# ethernet.net
KiCad netlist of a schematic drawn in Altium Designer
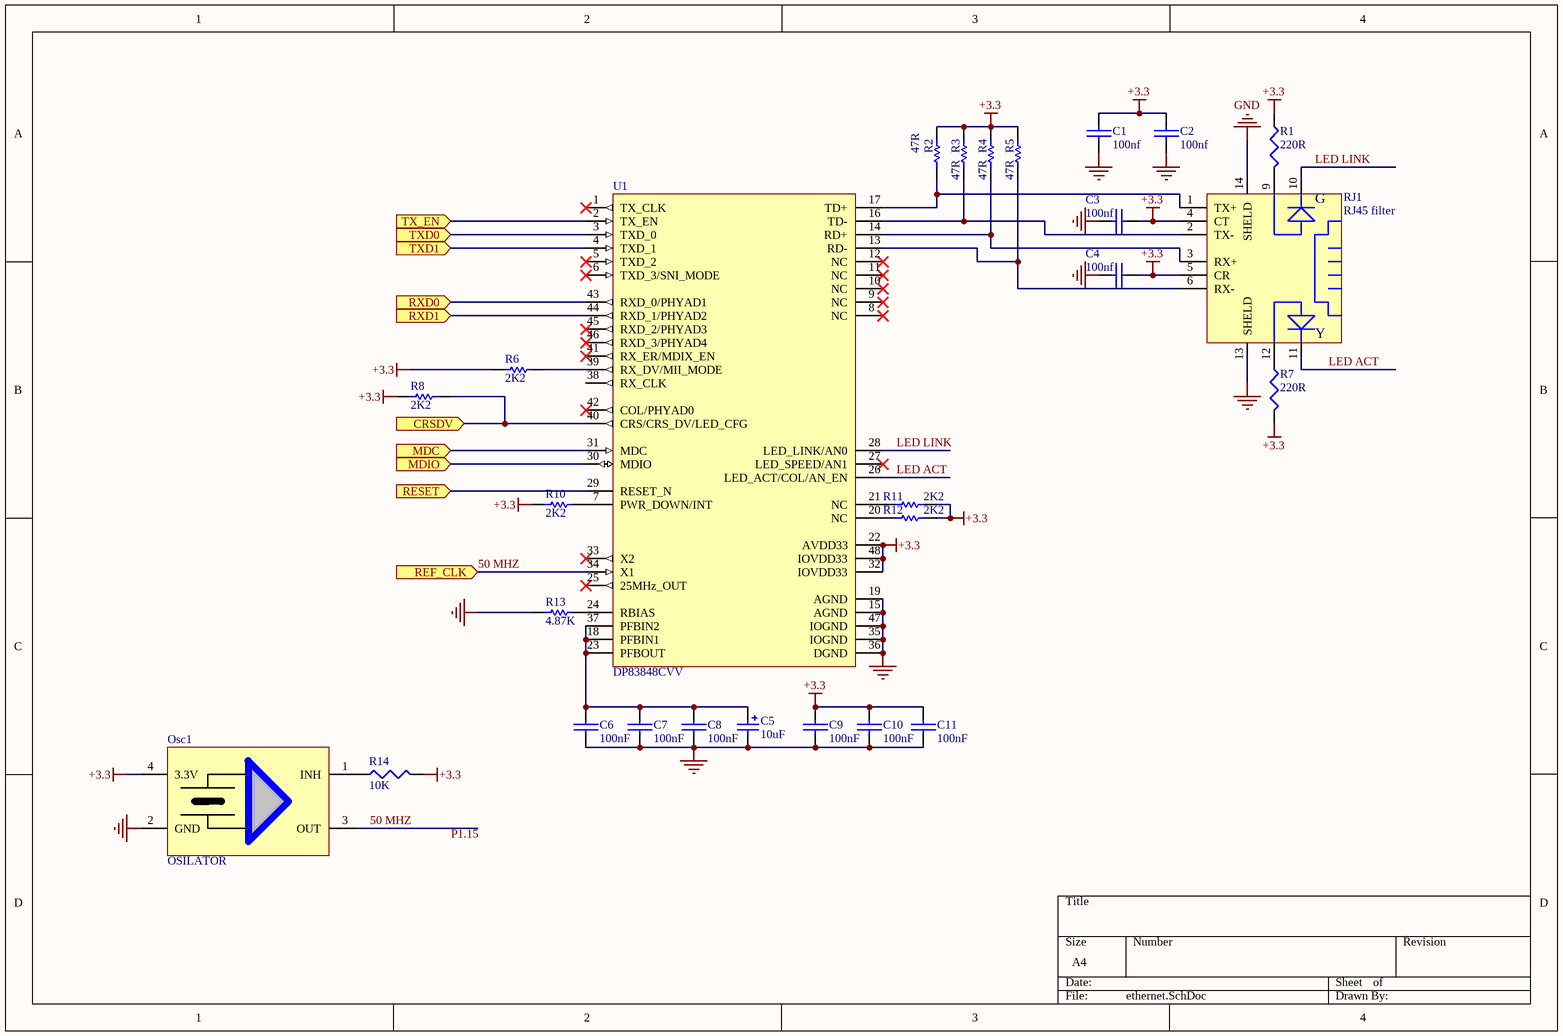
[diagram p0: ethernet.SchDoc]

(export (version "E")
  (design (tool "Eeschema 10.0.6"))
  (components
    (comp (ref "C1") (value "100nf") (footprint "1206") (libsource (lib "") (part "CAP_1")))
    (comp (ref "C2") (value "100nf") (footprint "1206") (libsource (lib "") (part "CAP_1")))
    (comp (ref "C3") (value "100nf") (footprint "1206") (libsource (lib "") (part "CAP_1")))
    (comp (ref "C4") (value "100nf") (footprint "1206") (libsource (lib "") (part "CAP_1")))
    (comp (ref "C5")
      (value "10uF")
      (footprint "cap10")
      (description "Polarized Capacitor (Radial)")
      (fields (field (name "PUBLISHER") "Altium Limited"))
      (libsource (lib "Miscellaneous Devices") (part "Cap Pol1"))
    )
    (comp (ref "C6")
      (value "100nF")
      (footprint "0805")
      (description "Capacitor")
      (libsource (lib "*") (part "CAP"))
    )
    (comp (ref "C7")
      (value "100nF")
      (footprint "0805")
      (description "Capacitor")
      (libsource (lib "*") (part "CAP"))
    )
    (comp (ref "C8")
      (value "100nF")
      (footprint "0805")
      (description "Capacitor")
      (libsource (lib "*") (part "CAP"))
    )
    (comp (ref "C9")
      (value "100nF")
      (footprint "0805")
      (description "Capacitor")
      (libsource (lib "*") (part "CAP"))
    )
    (comp (ref "C10")
      (value "100nF")
      (footprint "0805")
      (description "Capacitor")
      (libsource (lib "*") (part "CAP"))
    )
    (comp (ref "C11")
      (value "100nF")
      (footprint "0805")
      (description "Capacitor")
      (libsource (lib "*") (part "CAP"))
    )
    (comp (ref "Osc1")
      (value "OSILATOR")
      (footprint "XTAL_5X7")
      (libsource (lib "New Lib") (part "OSILATOR"))
    )
    (comp (ref "R1")
      (value "220R")
      (footprint "1206")
      (description "Resistor")
      (fields (field (name "PUBLISHER") "Altium Limited"))
      (libsource (lib "Miscellaneous Devices") (part "Res3"))
    )
    (comp (ref "R2")
      (value "47R")
      (footprint "1206")
      (description "Resistor")
      (fields (field (name "PUBLISHER") "Altium Limited"))
      (libsource (lib "Miscellaneous Devices") (part "Res1"))
    )
    (comp (ref "R3")
      (value "47R")
      (footprint "1206")
      (description "Resistor")
      (fields (field (name "PUBLISHER") "Altium Limited"))
      (libsource (lib "Miscellaneous Devices") (part "Res1"))
    )
    (comp (ref "R4")
      (value "47R")
      (footprint "1206")
      (description "Resistor")
      (fields (field (name "PUBLISHER") "Altium Limited"))
      (libsource (lib "Miscellaneous Devices") (part "Res1"))
    )
    (comp (ref "R5")
      (value "47R")
      (footprint "1206")
      (description "Resistor")
      (fields (field (name "PUBLISHER") "Altium Limited"))
      (libsource (lib "Miscellaneous Devices") (part "Res1"))
    )
    (comp (ref "R6")
      (value "2K2")
      (footprint "1206")
      (description "Resistor")
      (fields (field (name "PUBLISHER") "Altium Limited"))
      (libsource (lib "Miscellaneous Devices") (part "Res1"))
    )
    (comp (ref "R7")
      (value "220R")
      (footprint "1206")
      (description "Resistor")
      (fields (field (name "PUBLISHER") "Altium Limited"))
      (libsource (lib "Miscellaneous Devices") (part "Res3"))
    )
    (comp (ref "R8")
      (value "2K2")
      (footprint "1206")
      (description "Resistor")
      (fields (field (name "PUBLISHER") "Altium Limited"))
      (libsource (lib "Miscellaneous Devices") (part "Res1"))
    )
    (comp (ref "R10")
      (value "2K2")
      (footprint "1206")
      (description "Resistor")
      (fields (field (name "PUBLISHER") "Altium Limited"))
      (libsource (lib "Miscellaneous Devices") (part "Res1"))
    )
    (comp (ref "R11")
      (value "2K2")
      (footprint "1206")
      (description "Resistor")
      (fields (field (name "PUBLISHER") "Altium Limited"))
      (libsource (lib "Miscellaneous Devices") (part "Res1"))
    )
    (comp (ref "R12")
      (value "2K2")
      (footprint "1206")
      (description "Resistor")
      (fields (field (name "PUBLISHER") "Altium Limited"))
      (libsource (lib "Miscellaneous Devices") (part "Res1"))
    )
    (comp (ref "R13")
      (value "4.87K")
      (footprint "1206")
      (description "Resistor")
      (fields (field (name "PUBLISHER") "Altium Limited"))
      (libsource (lib "Miscellaneous Devices") (part "Res1"))
    )
    (comp (ref "R14")
      (value "10K")
      (footprint "1206")
      (description "Resistor")
      (fields (field (name "PUBLISHER") "Altium Limited"))
      (libsource (lib "Miscellaneous Devices") (part "Res3"))
    )
    (comp (ref "RJ1")
      (value "RJ45 filter")
      (footprint "RJ45LED")
      (libsource (lib "Schlib1") (part "RJ45_led_filter"))
    )
    (comp (ref "U1")
      (value "DP83848CVV")
      (footprint "TQFP48_M")
      (libsource (lib "MB784") (part "DP83848CVV"))
    )
  )
  (nets
    (net (code "1") (name "+3.3") (class "Default")
      (node (ref "C1") (pin "2") (pintype "passive"))
      (node (ref "C10") (pin "2") (pinfunction "2_2") (pintype "passive"))
      (node (ref "C11") (pin "2") (pinfunction "2_2") (pintype "passive"))
      (node (ref "C2") (pin "2") (pintype "passive"))
      (node (ref "C3") (pin "2") (pintype "passive"))
      (node (ref "C4") (pin "2") (pintype "passive"))
      (node (ref "C9") (pin "1") (pinfunction "1_1") (pintype "passive"))
      (node (ref "Osc1") (pin "4") (pinfunction "3.3V_4") (pintype "passive"))
      (node (ref "R1") (pin "1") (pinfunction "1_1") (pintype "passive"))
      (node (ref "R10") (pin "1") (pinfunction "1_1") (pintype "passive"))
      (node (ref "R11") (pin "2") (pinfunction "2_2") (pintype "passive"))
      (node (ref "R12") (pin "2") (pinfunction "2_2") (pintype "passive"))
      (node (ref "R14") (pin "2") (pinfunction "2_2") (pintype "passive"))
      (node (ref "R2") (pin "2") (pinfunction "2_2") (pintype "passive"))
      (node (ref "R3") (pin "2") (pinfunction "2_2") (pintype "passive"))
      (node (ref "R4") (pin "2") (pinfunction "2_2") (pintype "passive"))
      (node (ref "R5") (pin "2") (pinfunction "2_2") (pintype "passive"))
      (node (ref "R6") (pin "1") (pinfunction "1_1") (pintype "passive"))
      (node (ref "R7") (pin "1") (pinfunction "1_1") (pintype "passive"))
      (node (ref "R8") (pin "1") (pinfunction "1_1") (pintype "passive"))
      (node (ref "RJ1") (pin "4") (pinfunction "CT_4") (pintype "passive"))
      (node (ref "RJ1") (pin "5") (pinfunction "CR_5") (pintype "passive"))
      (node (ref "U1") (pin "22") (pinfunction "AVDD33_22") (pintype "passive"))
      (node (ref "U1") (pin "32") (pinfunction "IOVDD33_32") (pintype "passive"))
      (node (ref "U1") (pin "48") (pinfunction "IOVDD33_48") (pintype "passive"))
    )
    (net (code "2") (name "/50 MHZ") (class "Default")
      (node (ref "Osc1") (pin "3") (pinfunction "OUT_3") (pintype "passive"))
      (node (ref "U1") (pin "34") (pinfunction "X1_34") (pintype "input"))
    )
    (net (code "3") (name "/CRSDV") (class "Default")
      (node (ref "R8") (pin "2") (pinfunction "2_2") (pintype "passive"))
      (node (ref "U1") (pin "40") (pinfunction "CRS/CRS_DV/LED_CFG_40") (pintype "output"))
    )
    (net (code "4") (name "/LED ACT") (class "Default")
      (node (ref "RJ1") (pin "11") (pinfunction "ledy-_11") (pintype "passive"))
      (node (ref "U1") (pin "26") (pinfunction "LED_ACT/COL/AN_EN_26") (pintype "passive"))
    )
    (net (code "5") (name "/LED LINK") (class "Default")
      (node (ref "RJ1") (pin "10") (pinfunction "ledg-_10") (pintype "passive"))
      (node (ref "U1") (pin "28") (pinfunction "LED_LINK/AN0_28") (pintype "passive"))
    )
    (net (code "6") (name "/MDC") (class "Default")
      (node (ref "U1") (pin "31") (pinfunction "MDC_31") (pintype "input"))
    )
    (net (code "7") (name "/MDIO") (class "Default")
      (node (ref "U1") (pin "30") (pinfunction "MDIO_30") (pintype "bidirectional"))
    )
    (net (code "9") (name "/RESET") (class "Default")
      (node (ref "U1") (pin "29") (pinfunction "RESET_N_29") (pintype "passive"))
    )
    (net (code "10") (name "/RXD0") (class "Default")
      (node (ref "U1") (pin "43") (pinfunction "RXD_0/PHYAD1_43") (pintype "output"))
    )
    (net (code "11") (name "/RXD1") (class "Default")
      (node (ref "U1") (pin "44") (pinfunction "RXD_1/PHYAD2_44") (pintype "output"))
    )
    (net (code "12") (name "/TXD0") (class "Default")
      (node (ref "U1") (pin "3") (pinfunction "TXD_0_3") (pintype "input"))
    )
    (net (code "13") (name "/TXD1") (class "Default")
      (node (ref "U1") (pin "4") (pinfunction "TXD_1_4") (pintype "input"))
    )
    (net (code "14") (name "/TX_EN") (class "Default")
      (node (ref "U1") (pin "2") (pinfunction "TX_EN_2") (pintype "input"))
    )
    (net (code "15") (name "GND") (class "Default")
      (node (ref "C1") (pin "1") (pintype "passive"))
      (node (ref "C10") (pin "1") (pinfunction "1_1") (pintype "passive"))
      (node (ref "C11") (pin "1") (pinfunction "1_1") (pintype "passive"))
      (node (ref "C2") (pin "1") (pintype "passive"))
      (node (ref "C3") (pin "1") (pintype "passive"))
      (node (ref "C4") (pin "1") (pintype "passive"))
      (node (ref "C5") (pin "2") (pinfunction "2_2") (pintype "passive"))
      (node (ref "C6") (pin "2") (pinfunction "2_2") (pintype "passive"))
      (node (ref "C7") (pin "1") (pinfunction "1_1") (pintype "passive"))
      (node (ref "C8") (pin "1") (pinfunction "1_1") (pintype "passive"))
      (node (ref "C9") (pin "2") (pinfunction "2_2") (pintype "passive"))
      (node (ref "Osc1") (pin "2") (pinfunction "GND_2") (pintype "passive"))
      (node (ref "R13") (pin "1") (pinfunction "1_1") (pintype "passive"))
      (node (ref "RJ1") (pin "13") (pinfunction "SHELD_13") (pintype "passive"))
      (node (ref "RJ1") (pin "14") (pinfunction "SHELD_14") (pintype "passive"))
      (node (ref "U1") (pin "15") (pinfunction "AGND_15") (pintype "passive"))
      (node (ref "U1") (pin "19") (pinfunction "AGND_19") (pintype "passive"))
      (node (ref "U1") (pin "35") (pinfunction "IOGND_35") (pintype "passive"))
      (node (ref "U1") (pin "36") (pinfunction "DGND_36") (pintype "passive"))
      (node (ref "U1") (pin "47") (pinfunction "IOGND_47") (pintype "passive"))
    )
    (net (code "16") (name "Net-(Osc1-INH)") (class "Default")
      (node (ref "Osc1") (pin "1") (pinfunction "INH_1") (pintype "passive"))
      (node (ref "R14") (pin "1") (pinfunction "1_1") (pintype "passive"))
    )
    (net (code "17") (name "Net-(R11-Pad1)") (class "Default")
      (node (ref "R11") (pin "1") (pinfunction "1_1") (pintype "passive"))
      (node (ref "U1") (pin "21") (pinfunction "NC_21") (pintype "passive"))
    )
    (net (code "18") (name "Net-(R12-Pad1)") (class "Default")
      (node (ref "R12") (pin "1") (pinfunction "1_1") (pintype "passive"))
      (node (ref "U1") (pin "20") (pinfunction "NC_20") (pintype "passive"))
    )
    (net (code "19") (name "Net-(RJ1-RX+)") (class "Default")
      (node (ref "R4") (pin "1") (pinfunction "1_1") (pintype "passive"))
      (node (ref "RJ1") (pin "3") (pinfunction "RX+_3") (pintype "passive"))
      (node (ref "U1") (pin "14") (pinfunction "RD+_14") (pintype "passive"))
    )
    (net (code "20") (name "Net-(RJ1-RX-)") (class "Default")
      (node (ref "R5") (pin "1") (pinfunction "1_1") (pintype "passive"))
      (node (ref "RJ1") (pin "6") (pinfunction "RX-_6") (pintype "passive"))
      (node (ref "U1") (pin "13") (pinfunction "RD-_13") (pintype "passive"))
    )
    (net (code "21") (name "Net-(RJ1-TX+)") (class "Default")
      (node (ref "R2") (pin "1") (pinfunction "1_1") (pintype "passive"))
      (node (ref "RJ1") (pin "1") (pinfunction "TX+_1") (pintype "passive"))
      (node (ref "U1") (pin "17") (pinfunction "TD+_17") (pintype "passive"))
    )
    (net (code "22") (name "Net-(RJ1-TX-)") (class "Default")
      (node (ref "R3") (pin "1") (pinfunction "1_1") (pintype "passive"))
      (node (ref "RJ1") (pin "2") (pinfunction "TX-_2") (pintype "passive"))
      (node (ref "U1") (pin "16") (pinfunction "TD-_16") (pintype "passive"))
    )
    (net (code "23") (name "Net-(RJ1-ledg+)") (class "Default")
      (node (ref "R1") (pin "2") (pinfunction "2_2") (pintype "passive"))
      (node (ref "RJ1") (pin "9") (pinfunction "ledg+_9") (pintype "passive"))
    )
    (net (code "24") (name "Net-(RJ1-ledy+)") (class "Default")
      (node (ref "R7") (pin "2") (pinfunction "2_2") (pintype "passive"))
      (node (ref "RJ1") (pin "12") (pinfunction "ledy+_12") (pintype "passive"))
    )
    (net (code "25") (name "Net-(U1-PFBIN1)") (class "Default")
      (node (ref "C5") (pin "1") (pinfunction "1_1") (pintype "passive"))
      (node (ref "C6") (pin "1") (pinfunction "1_1") (pintype "passive"))
      (node (ref "C7") (pin "2") (pinfunction "2_2") (pintype "passive"))
      (node (ref "C8") (pin "2") (pinfunction "2_2") (pintype "passive"))
      (node (ref "U1") (pin "18") (pinfunction "PFBIN1_18") (pintype "passive"))
      (node (ref "U1") (pin "23") (pinfunction "PFBOUT_23") (pintype "passive"))
      (node (ref "U1") (pin "37") (pinfunction "PFBIN2_37") (pintype "passive"))
    )
    (net (code "26") (name "Net-(U1-PWR_DOWN{slash}INT)") (class "Default")
      (node (ref "R10") (pin "2") (pinfunction "2_2") (pintype "passive"))
      (node (ref "U1") (pin "7") (pinfunction "PWR_DOWN/INT_7") (pintype "passive"))
    )
    (net (code "27") (name "Net-(U1-RBIAS)") (class "Default")
      (node (ref "R13") (pin "2") (pinfunction "2_2") (pintype "passive"))
      (node (ref "U1") (pin "24") (pinfunction "RBIAS_24") (pintype "passive"))
    )
    (net (code "28") (name "Net-(U1-RX_DV{slash}MII_MODE)") (class "Default")
      (node (ref "R6") (pin "2") (pinfunction "2_2") (pintype "passive"))
      (node (ref "U1") (pin "39") (pinfunction "RX_DV/MII_MODE_39") (pintype "output"))
    )
    (net (code "29") (name "unconnected-(U1-25MHz_OUT-Pad25)") (class "Default")
      (node (ref "U1") (pin "25") (pinfunction "25MHz_OUT_25") (pintype "output+no_connect"))
    )
    (net (code "30") (name "unconnected-(U1-COL{slash}PHYAD0-Pad42)") (class "Default")
      (node (ref "U1") (pin "42") (pinfunction "COL/PHYAD0_42") (pintype "output+no_connect"))
    )
    (net (code "31") (name "unconnected-(U1-LED_SPEED{slash}AN1-Pad27)") (class "Default")
      (node (ref "U1") (pin "27") (pinfunction "LED_SPEED/AN1_27") (pintype "passive+no_connect"))
    )
    (net (code "32") (name "unconnected-(U1-NC-Pad8)") (class "Default")
      (node (ref "U1") (pin "8") (pinfunction "NC_8") (pintype "passive+no_connect"))
    )
    (net (code "33") (name "unconnected-(U1-NC-Pad9)") (class "Default")
      (node (ref "U1") (pin "9") (pinfunction "NC_9") (pintype "passive+no_connect"))
    )
    (net (code "34") (name "unconnected-(U1-NC-Pad10)") (class "Default")
      (node (ref "U1") (pin "10") (pinfunction "NC_10") (pintype "passive+no_connect"))
    )
    (net (code "35") (name "unconnected-(U1-NC-Pad11)") (class "Default")
      (node (ref "U1") (pin "11") (pinfunction "NC_11") (pintype "passive+no_connect"))
    )
    (net (code "36") (name "unconnected-(U1-NC-Pad12)") (class "Default")
      (node (ref "U1") (pin "12") (pinfunction "NC_12") (pintype "passive+no_connect"))
    )
    (net (code "37") (name "unconnected-(U1-RXD_2{slash}PHYAD3-Pad45)") (class "Default")
      (node (ref "U1") (pin "45") (pinfunction "RXD_2/PHYAD3_45") (pintype "output+no_connect"))
    )
    (net (code "38") (name "unconnected-(U1-RXD_3{slash}PHYAD4-Pad46)") (class "Default")
      (node (ref "U1") (pin "46") (pinfunction "RXD_3/PHYAD4_46") (pintype "output+no_connect"))
    )
    (net (code "39") (name "unconnected-(U1-RX_CLK-Pad38)") (class "Default")
      (node (ref "U1") (pin "38") (pinfunction "RX_CLK_38") (pintype "output"))
    )
    (net (code "40") (name "unconnected-(U1-RX_ER{slash}MDIX_EN-Pad41)") (class "Default")
      (node (ref "U1") (pin "41") (pinfunction "RX_ER/MDIX_EN_41") (pintype "output+no_connect"))
    )
    (net (code "41") (name "unconnected-(U1-TXD_2-Pad5)") (class "Default")
      (node (ref "U1") (pin "5") (pinfunction "TXD_2_5") (pintype "input+no_connect"))
    )
    (net (code "42") (name "unconnected-(U1-TXD_3{slash}SNI_MODE-Pad6)") (class "Default")
      (node (ref "U1") (pin "6") (pinfunction "TXD_3/SNI_MODE_6") (pintype "input+no_connect"))
    )
    (net (code "43") (name "unconnected-(U1-TX_CLK-Pad1)") (class "Default")
      (node (ref "U1") (pin "1") (pinfunction "TX_CLK_1") (pintype "output+no_connect"))
    )
    (net (code "44") (name "unconnected-(U1-X2-Pad33)") (class "Default")
      (node (ref "U1") (pin "33") (pinfunction "X2_33") (pintype "output+no_connect"))
    )
  )
)
